# PCE_Trace_Power_test.net
KiCad netlist of a schematic drawn in EAGLE
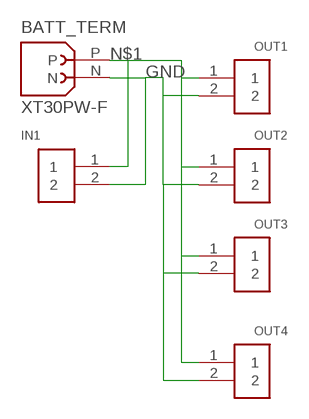
[diagram p0: schematic, sheet 1]

(export (version "E")
  (design (tool "Eeschema 10.0.6"))
  (components
    (comp (ref "BATT_TERM")
      (value "XT30PW-F")
      (footprint "eagle-import:AMASS_XT30PW-F")
      (fields (field (name "MF") "amass"))
      (libsource (lib "eagle-import") (part "XT30PW-F"))
    )
    (comp (ref "IN1")
      (value "282837-2")
      (footprint "eagle-import:TE_282837-2")
      (fields (field (name "MF") "TE Connectivity"))
      (libsource (lib "eagle-import") (part "282837-2"))
    )
    (comp (ref "OUT1")
      (value "282837-2")
      (footprint "eagle-import:TE_282837-2")
      (fields (field (name "MF") "TE Connectivity"))
      (libsource (lib "eagle-import") (part "282837-2"))
    )
    (comp (ref "OUT2")
      (value "282837-2")
      (footprint "eagle-import:TE_282837-2")
      (fields (field (name "MF") "TE Connectivity"))
      (libsource (lib "eagle-import") (part "282837-2"))
    )
    (comp (ref "OUT3")
      (value "282837-2")
      (footprint "eagle-import:TE_282837-2")
      (fields (field (name "MF") "TE Connectivity"))
      (libsource (lib "eagle-import") (part "282837-2"))
    )
    (comp (ref "OUT4")
      (value "282837-2")
      (footprint "eagle-import:TE_282837-2")
      (fields (field (name "MF") "TE Connectivity"))
      (libsource (lib "eagle-import") (part "282837-2"))
    )
  )
  (nets
    (net (code "1") (name "/GND") (class "Default")
      (node (ref "BATT_TERM") (pin "N") (pinfunction "N_N") (pintype "power_in"))
      (node (ref "IN1") (pin "2") (pinfunction "2_2") (pintype "passive"))
      (node (ref "OUT1") (pin "2") (pinfunction "2_2") (pintype "passive"))
      (node (ref "OUT2") (pin "2") (pinfunction "2_2") (pintype "passive"))
      (node (ref "OUT3") (pin "2") (pinfunction "2_2") (pintype "passive"))
      (node (ref "OUT4") (pin "2") (pinfunction "2_2") (pintype "passive"))
    )
    (net (code "2") (name "/N$1") (class "Default")
      (node (ref "BATT_TERM") (pin "P") (pinfunction "P_P") (pintype "power_in"))
      (node (ref "IN1") (pin "1") (pinfunction "1_1") (pintype "passive"))
      (node (ref "OUT1") (pin "1") (pinfunction "1_1") (pintype "passive"))
      (node (ref "OUT2") (pin "1") (pinfunction "1_1") (pintype "passive"))
      (node (ref "OUT3") (pin "1") (pinfunction "1_1") (pintype "passive"))
      (node (ref "OUT4") (pin "1") (pinfunction "1_1") (pintype "passive"))
    )
  )
)
